# 808_Kick.net
KiCad netlist of a schematic drawn in EAGLE
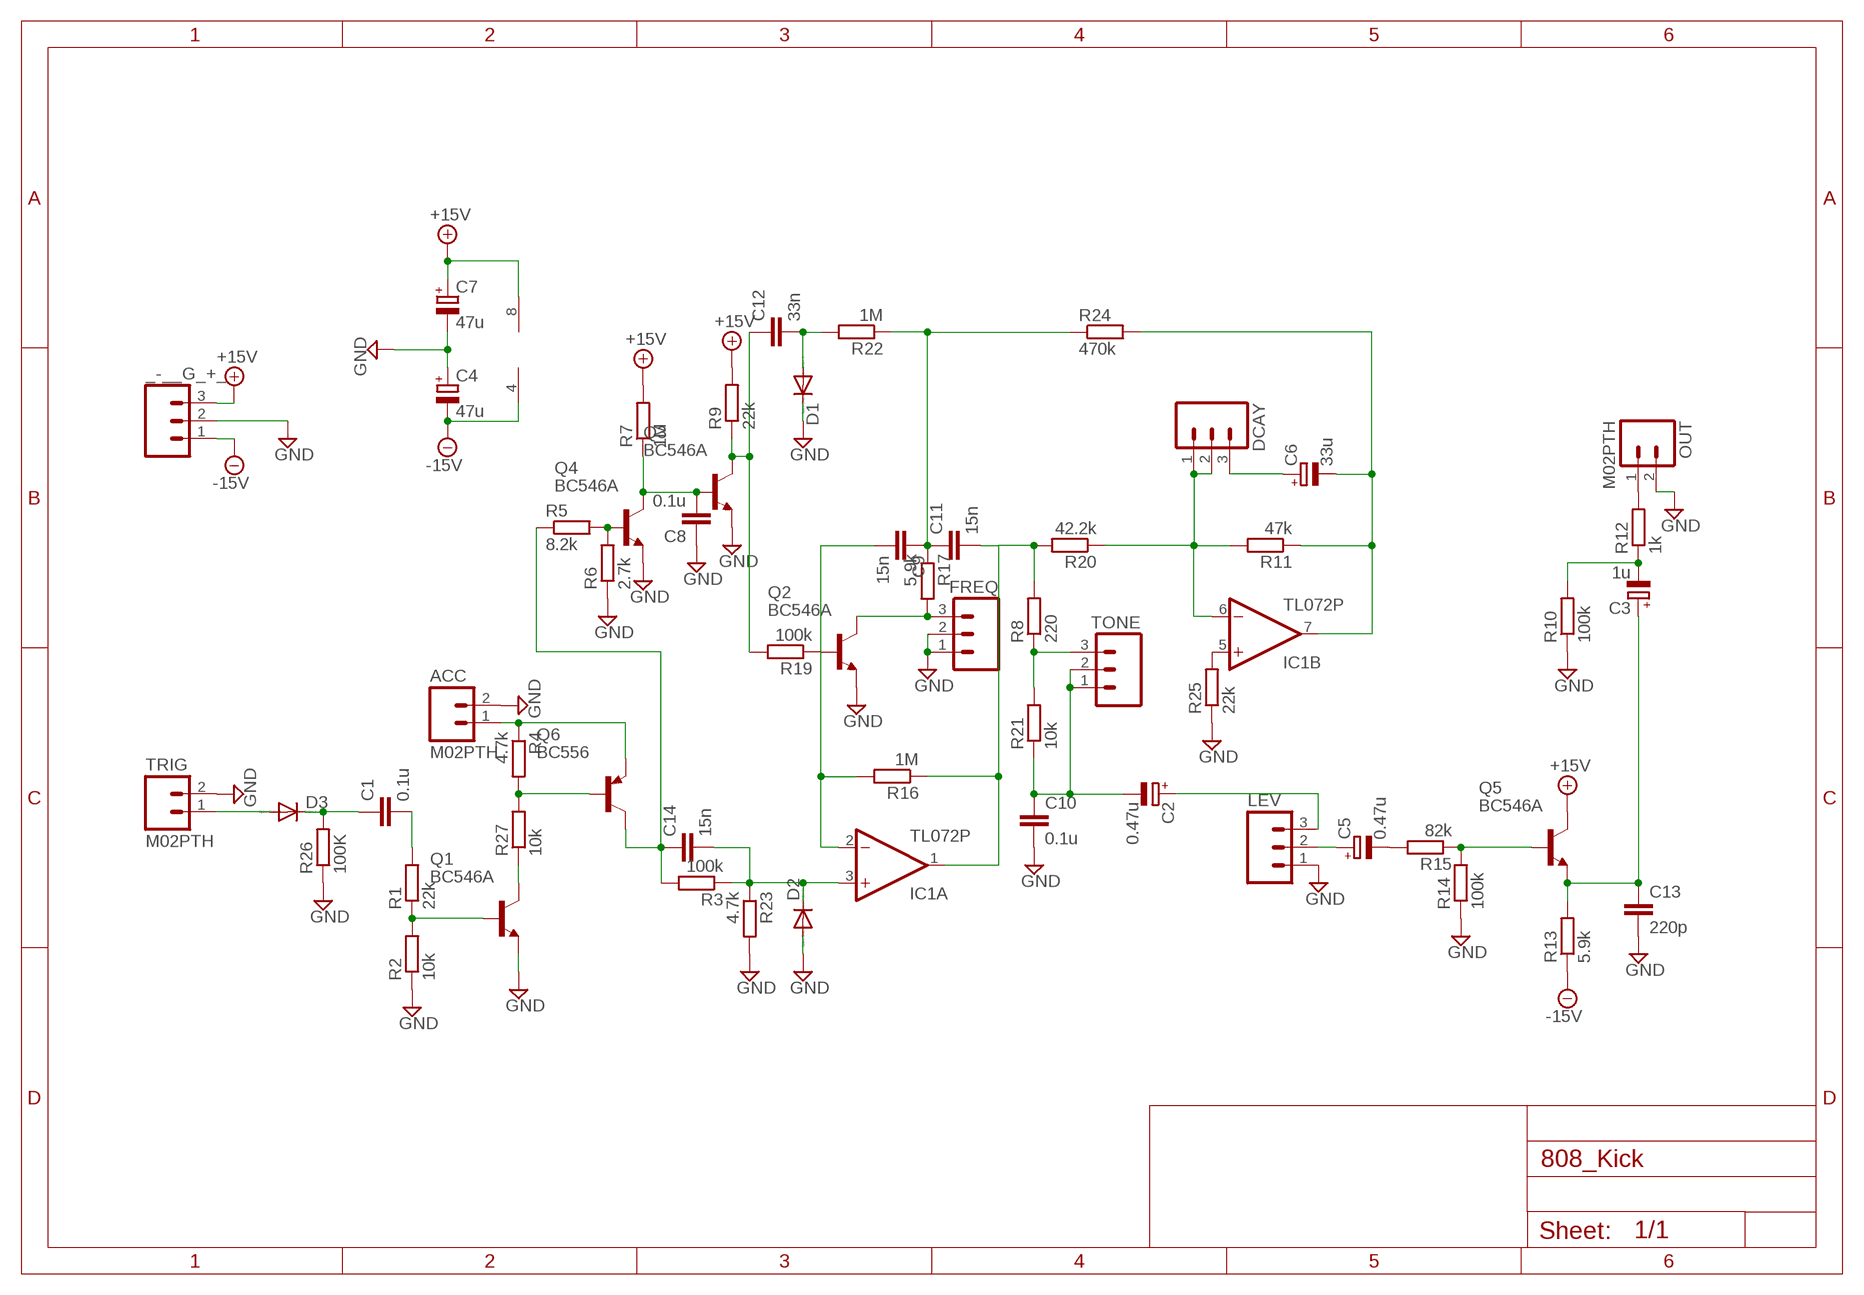
[diagram p0: schematic, sheet 1]

(export (version "E")
  (design (tool "Eeschema 10.0.6"))
  (components
    (comp (ref "ACC")
      (value "M02PTH")
      (footprint "eagle-import:1X02")
      (libsource (lib "eagle-import") (part "M02PTH"))
    )
    (comp (ref "C1")
      (value "0.1u")
      (footprint "eagle-import:C025-024X044")
      (libsource (lib "eagle-import") (part "C-EU025-024X044"))
    )
    (comp (ref "C2")
      (value "0.47u")
      (footprint "eagle-import:E2,5-6E")
      (libsource (lib "eagle-import") (part "CPOL-EUE2,5-6E"))
    )
    (comp (ref "C3")
      (value "1u")
      (footprint "eagle-import:E2,5-6E")
      (libsource (lib "eagle-import") (part "CPOL-EUE2,5-6E"))
    )
    (comp (ref "C4")
      (value "47u")
      (footprint "eagle-import:E2,5-6E")
      (libsource (lib "eagle-import") (part "CPOL-EUE2,5-6E"))
    )
    (comp (ref "C5")
      (value "0.47u")
      (footprint "eagle-import:E2,5-6E")
      (libsource (lib "eagle-import") (part "CPOL-EUE2,5-6E"))
    )
    (comp (ref "C6")
      (value "33u")
      (footprint "eagle-import:E2,5-6E")
      (libsource (lib "eagle-import") (part "CPOL-EUE2,5-6E"))
    )
    (comp (ref "C7")
      (value "47u")
      (footprint "eagle-import:E2,5-6E")
      (libsource (lib "eagle-import") (part "CPOL-EUE2,5-6E"))
    )
    (comp (ref "C8")
      (value "0.1u")
      (footprint "eagle-import:C025-024X044")
      (libsource (lib "eagle-import") (part "C-EU025-024X044"))
    )
    (comp (ref "C9")
      (value "15n")
      (footprint "eagle-import:C025-024X044")
      (libsource (lib "eagle-import") (part "C-EU025-024X044"))
    )
    (comp (ref "C10")
      (value "0.1u")
      (footprint "eagle-import:C025-024X044")
      (libsource (lib "eagle-import") (part "C-EU025-024X044"))
    )
    (comp (ref "C11")
      (value "15n")
      (footprint "eagle-import:C025-024X044")
      (libsource (lib "eagle-import") (part "C-EU025-024X044"))
    )
    (comp (ref "C12")
      (value "33n")
      (footprint "eagle-import:C025-024X044")
      (libsource (lib "eagle-import") (part "C-EU025-024X044"))
    )
    (comp (ref "C13")
      (value "220p")
      (footprint "eagle-import:C025-024X044")
      (libsource (lib "eagle-import") (part "C-EU025-024X044"))
    )
    (comp (ref "C14")
      (value "15n")
      (footprint "eagle-import:C025-024X044")
      (libsource (lib "eagle-import") (part "C-EU025-024X044"))
    )
    (comp (ref "D1")
      (value "DIODE-D-2.5")
      (footprint "eagle-import:D-2.5")
      (libsource (lib "eagle-import") (part "DIODE-D-2.5"))
    )
    (comp (ref "D2")
      (value "DIODE-D-2.5")
      (footprint "eagle-import:D-2.5")
      (libsource (lib "eagle-import") (part "DIODE-D-2.5"))
    )
    (comp (ref "D3")
      (value "DIODE-D-2.5")
      (footprint "eagle-import:D-2.5")
      (libsource (lib "eagle-import") (part "DIODE-D-2.5"))
    )
    (comp (ref "DCAY")
      (value "M03PTH")
      (footprint "eagle-import:1X03")
      (libsource (lib "eagle-import") (part "M03PTH"))
    )
    (comp (ref "FREQ")
      (value "M03PTH")
      (footprint "eagle-import:1X03")
      (libsource (lib "eagle-import") (part "M03PTH"))
    )
    (comp (ref "IC1")
      (value "TL072P")
      (footprint "eagle-import:DIL08")
      (libsource (lib "eagle-import") (part "TL072P"))
    )
    (comp (ref "LEV")
      (value "M03PTH")
      (footprint "eagle-import:1X03")
      (libsource (lib "eagle-import") (part "M03PTH"))
    )
    (comp (ref "OUT")
      (value "M02PTH")
      (footprint "eagle-import:1X02")
      (libsource (lib "eagle-import") (part "M02PTH"))
    )
    (comp (ref "Q1")
      (value "BC546A")
      (footprint "eagle-import:TO92-EBC")
      (libsource (lib "eagle-import") (part "BC546A"))
    )
    (comp (ref "Q2")
      (value "BC546A")
      (footprint "eagle-import:TO92-EBC")
      (libsource (lib "eagle-import") (part "BC546A"))
    )
    (comp (ref "Q3")
      (value "BC546A")
      (footprint "eagle-import:TO92-EBC")
      (libsource (lib "eagle-import") (part "BC546A"))
    )
    (comp (ref "Q4")
      (value "BC546A")
      (footprint "eagle-import:TO92-EBC")
      (libsource (lib "eagle-import") (part "BC546A"))
    )
    (comp (ref "Q5")
      (value "BC546A")
      (footprint "eagle-import:TO92-EBC")
      (libsource (lib "eagle-import") (part "BC546A"))
    )
    (comp (ref "Q6")
      (value "BC556")
      (footprint "eagle-import:TO92-EBC")
      (libsource (lib "eagle-import") (part "BC556"))
    )
    (comp (ref "R1")
      (value "22k")
      (footprint "eagle-import:0207_2V")
      (libsource (lib "eagle-import") (part "R-EU_0207/2V"))
    )
    (comp (ref "R2")
      (value "10k")
      (footprint "eagle-import:0207_2V")
      (libsource (lib "eagle-import") (part "R-EU_0207/2V"))
    )
    (comp (ref "R3")
      (value "100k")
      (footprint "eagle-import:0207_2V")
      (libsource (lib "eagle-import") (part "R-EU_0207/2V"))
    )
    (comp (ref "R4")
      (value "4.7k")
      (footprint "eagle-import:0207_2V")
      (libsource (lib "eagle-import") (part "R-EU_0207/2V"))
    )
    (comp (ref "R5")
      (value "8.2k")
      (footprint "eagle-import:0207_2V")
      (libsource (lib "eagle-import") (part "R-EU_0207/2V"))
    )
    (comp (ref "R6")
      (value "2.7k")
      (footprint "eagle-import:0207_2V")
      (libsource (lib "eagle-import") (part "R-EU_0207/2V"))
    )
    (comp (ref "R7")
      (value "1M")
      (footprint "eagle-import:0207_2V")
      (libsource (lib "eagle-import") (part "R-EU_0207/2V"))
    )
    (comp (ref "R8")
      (value "220")
      (footprint "eagle-import:0207_2V")
      (libsource (lib "eagle-import") (part "R-EU_0207/2V"))
    )
    (comp (ref "R9")
      (value "22k")
      (footprint "eagle-import:0207_2V")
      (libsource (lib "eagle-import") (part "R-EU_0207/2V"))
    )
    (comp (ref "R10")
      (value "100k")
      (footprint "eagle-import:0207_2V")
      (libsource (lib "eagle-import") (part "R-EU_0207/2V"))
    )
    (comp (ref "R11")
      (value "47k")
      (footprint "eagle-import:0207_2V")
      (libsource (lib "eagle-import") (part "R-EU_0207/2V"))
    )
    (comp (ref "R12")
      (value "1k")
      (footprint "eagle-import:0207_2V")
      (libsource (lib "eagle-import") (part "R-EU_0207/2V"))
    )
    (comp (ref "R13")
      (value "5.9k")
      (footprint "eagle-import:0207_2V")
      (libsource (lib "eagle-import") (part "R-EU_0207/2V"))
    )
    (comp (ref "R14")
      (value "100k")
      (footprint "eagle-import:0207_2V")
      (libsource (lib "eagle-import") (part "R-EU_0207/2V"))
    )
    (comp (ref "R15")
      (value "82k")
      (footprint "eagle-import:0207_2V")
      (libsource (lib "eagle-import") (part "R-EU_0207/2V"))
    )
    (comp (ref "R16")
      (value "1M")
      (footprint "eagle-import:0207_2V")
      (libsource (lib "eagle-import") (part "R-EU_0207/2V"))
    )
    (comp (ref "R17")
      (value "5.9k")
      (footprint "eagle-import:0207_2V")
      (libsource (lib "eagle-import") (part "R-EU_0207/2V"))
    )
    (comp (ref "R19")
      (value "100k")
      (footprint "eagle-import:0207_2V")
      (libsource (lib "eagle-import") (part "R-EU_0207/2V"))
    )
    (comp (ref "R20")
      (value "42.2k")
      (footprint "eagle-import:0207_2V")
      (libsource (lib "eagle-import") (part "R-EU_0207/2V"))
    )
    (comp (ref "R21")
      (value "10k")
      (footprint "eagle-import:0207_2V")
      (libsource (lib "eagle-import") (part "R-EU_0207/2V"))
    )
    (comp (ref "R22")
      (value "1M")
      (footprint "eagle-import:0207_2V")
      (libsource (lib "eagle-import") (part "R-EU_0207/2V"))
    )
    (comp (ref "R23")
      (value "4.7k")
      (footprint "eagle-import:0207_2V")
      (libsource (lib "eagle-import") (part "R-EU_0207/2V"))
    )
    (comp (ref "R24")
      (value "470k")
      (footprint "eagle-import:0207_2V")
      (libsource (lib "eagle-import") (part "R-EU_0207/2V"))
    )
    (comp (ref "R25")
      (value "22k")
      (footprint "eagle-import:0207_2V")
      (libsource (lib "eagle-import") (part "R-EU_0207/2V"))
    )
    (comp (ref "R26")
      (value "100K")
      (footprint "eagle-import:0207_2V")
      (libsource (lib "eagle-import") (part "R-EU_0207/2V"))
    )
    (comp (ref "R27")
      (value "10k")
      (footprint "eagle-import:0207_2V")
      (libsource (lib "eagle-import") (part "R-EU_0207/2V"))
    )
    (comp (ref "TONE")
      (value "M03PTH")
      (footprint "eagle-import:1X03")
      (libsource (lib "eagle-import") (part "M03PTH"))
    )
    (comp (ref "TRIG")
      (value "M02PTH")
      (footprint "eagle-import:1X02")
      (libsource (lib "eagle-import") (part "M02PTH"))
    )
    (comp (ref "_-__G_+_")
      (value "M03PTH")
      (footprint "eagle-import:1X03")
      (libsource (lib "eagle-import") (part "M03PTH"))
    )
  )
  (nets
    (net (code "1") (name "+15V") (class "Default")
      (node (ref "C7") (pin "+") (pinfunction "+_+") (pintype "passive"))
      (node (ref "IC1") (pin "8") (pinfunction "V+_8") (pintype "power_in"))
      (node (ref "Q5") (pin "C") (pinfunction "C_C") (pintype "passive"))
      (node (ref "R7") (pin "2") (pinfunction "2_2") (pintype "passive"))
      (node (ref "R9") (pin "2") (pinfunction "2_2") (pintype "passive"))
      (node (ref "_-__G_+_") (pin "3") (pinfunction "3_3") (pintype "passive"))
    )
    (net (code "2") (name "-15V") (class "Default")
      (node (ref "C4") (pin "-") (pinfunction "-_-") (pintype "passive"))
      (node (ref "IC1") (pin "4") (pinfunction "V-_4") (pintype "power_in"))
      (node (ref "R13") (pin "1") (pinfunction "1_1") (pintype "passive"))
      (node (ref "_-__G_+_") (pin "1") (pinfunction "1_1") (pintype "passive"))
    )
    (net (code "3") (name "GND") (class "Default")
      (node (ref "ACC") (pin "2") (pinfunction "2_2") (pintype "passive"))
      (node (ref "C10") (pin "2") (pinfunction "2_2") (pintype "passive"))
      (node (ref "C13") (pin "2") (pinfunction "2_2") (pintype "passive"))
      (node (ref "C4") (pin "+") (pinfunction "+_+") (pintype "passive"))
      (node (ref "C7") (pin "-") (pinfunction "-_-") (pintype "passive"))
      (node (ref "C8") (pin "1") (pinfunction "1_1") (pintype "passive"))
      (node (ref "D1") (pin "C") (pinfunction "C_C") (pintype "passive"))
      (node (ref "D2") (pin "A") (pinfunction "A_A") (pintype "passive"))
      (node (ref "FREQ") (pin "1") (pinfunction "1_1") (pintype "passive"))
      (node (ref "FREQ") (pin "2") (pinfunction "2_2") (pintype "passive"))
      (node (ref "LEV") (pin "1") (pinfunction "1_1") (pintype "passive"))
      (node (ref "OUT") (pin "2") (pinfunction "2_2") (pintype "passive"))
      (node (ref "Q1") (pin "E") (pinfunction "E_E") (pintype "passive"))
      (node (ref "Q2") (pin "E") (pinfunction "E_E") (pintype "passive"))
      (node (ref "Q3") (pin "E") (pinfunction "E_E") (pintype "passive"))
      (node (ref "Q4") (pin "E") (pinfunction "E_E") (pintype "passive"))
      (node (ref "R10") (pin "1") (pinfunction "1_1") (pintype "passive"))
      (node (ref "R14") (pin "1") (pinfunction "1_1") (pintype "passive"))
      (node (ref "R2") (pin "1") (pinfunction "1_1") (pintype "passive"))
      (node (ref "R23") (pin "2") (pinfunction "2_2") (pintype "passive"))
      (node (ref "R25") (pin "1") (pinfunction "1_1") (pintype "passive"))
      (node (ref "R26") (pin "1") (pinfunction "1_1") (pintype "passive"))
      (node (ref "R6") (pin "1") (pinfunction "1_1") (pintype "passive"))
      (node (ref "TRIG") (pin "2") (pinfunction "2_2") (pintype "passive"))
      (node (ref "_-__G_+_") (pin "2") (pinfunction "2_2") (pintype "passive"))
    )
    (net (code "4") (name "Net-(ACC-Pad1)") (class "Default")
      (node (ref "ACC") (pin "1") (pinfunction "1_1") (pintype "passive"))
      (node (ref "Q6") (pin "E") (pinfunction "E_E") (pintype "passive"))
      (node (ref "R4") (pin "1") (pinfunction "1_1") (pintype "passive"))
    )
    (net (code "5") (name "Net-(C1-Pad1)") (class "Default")
      (node (ref "C1") (pin "1") (pinfunction "1_1") (pintype "passive"))
      (node (ref "D3") (pin "C") (pinfunction "C_C") (pintype "passive"))
      (node (ref "R26") (pin "2") (pinfunction "2_2") (pintype "passive"))
    )
    (net (code "6") (name "Net-(C1-Pad2)") (class "Default")
      (node (ref "C1") (pin "2") (pinfunction "2_2") (pintype "passive"))
      (node (ref "R1") (pin "2") (pinfunction "2_2") (pintype "passive"))
    )
    (net (code "7") (name "Net-(C2-Pad+)") (class "Default")
      (node (ref "C2") (pin "+") (pinfunction "+_+") (pintype "passive"))
      (node (ref "LEV") (pin "3") (pinfunction "3_3") (pintype "passive"))
    )
    (net (code "8") (name "Net-(C3-Pad-)") (class "Default")
      (node (ref "C3") (pin "-") (pinfunction "-_-") (pintype "passive"))
      (node (ref "R10") (pin "2") (pinfunction "2_2") (pintype "passive"))
      (node (ref "R12") (pin "1") (pinfunction "1_1") (pintype "passive"))
    )
    (net (code "9") (name "Net-(C5-Pad+)") (class "Default")
      (node (ref "C5") (pin "+") (pinfunction "+_+") (pintype "passive"))
      (node (ref "LEV") (pin "2") (pinfunction "2_2") (pintype "passive"))
    )
    (net (code "10") (name "Net-(C5-Pad-)") (class "Default")
      (node (ref "C5") (pin "-") (pinfunction "-_-") (pintype "passive"))
      (node (ref "R15") (pin "2") (pinfunction "2_2") (pintype "passive"))
    )
    (net (code "11") (name "Net-(C6-Pad+)") (class "Default")
      (node (ref "C6") (pin "+") (pinfunction "+_+") (pintype "passive"))
      (node (ref "DCAY") (pin "3") (pinfunction "3_3") (pintype "passive"))
    )
    (net (code "12") (name "Net-(C8-Pad2)") (class "Default")
      (node (ref "C8") (pin "2") (pinfunction "2_2") (pintype "passive"))
      (node (ref "Q3") (pin "B") (pinfunction "B_B") (pintype "passive"))
      (node (ref "Q4") (pin "C") (pinfunction "C_C") (pintype "passive"))
      (node (ref "R7") (pin "1") (pinfunction "1_1") (pintype "passive"))
    )
    (net (code "13") (name "Net-(C10-Pad1)") (class "Default")
      (node (ref "C10") (pin "1") (pinfunction "1_1") (pintype "passive"))
      (node (ref "C2") (pin "-") (pinfunction "-_-") (pintype "passive"))
      (node (ref "R21") (pin "1") (pinfunction "1_1") (pintype "passive"))
      (node (ref "TONE") (pin "1") (pinfunction "1_1") (pintype "passive"))
      (node (ref "TONE") (pin "2") (pinfunction "2_2") (pintype "passive"))
    )
    (net (code "14") (name "Net-(C11-Pad1)") (class "Default")
      (node (ref "C11") (pin "1") (pinfunction "1_1") (pintype "passive"))
      (node (ref "C9") (pin "1") (pinfunction "1_1") (pintype "passive"))
      (node (ref "R17") (pin "1") (pinfunction "1_1") (pintype "passive"))
      (node (ref "R22") (pin "1") (pinfunction "1_1") (pintype "passive"))
      (node (ref "R24") (pin "1") (pinfunction "1_1") (pintype "passive"))
    )
    (net (code "15") (name "Net-(C12-Pad1)") (class "Default")
      (node (ref "C12") (pin "1") (pinfunction "1_1") (pintype "passive"))
      (node (ref "Q3") (pin "C") (pinfunction "C_C") (pintype "passive"))
      (node (ref "R19") (pin "2") (pinfunction "2_2") (pintype "passive"))
      (node (ref "R9") (pin "1") (pinfunction "1_1") (pintype "passive"))
    )
    (net (code "16") (name "Net-(C12-Pad2)") (class "Default")
      (node (ref "C12") (pin "2") (pinfunction "2_2") (pintype "passive"))
      (node (ref "D1") (pin "A") (pinfunction "A_A") (pintype "passive"))
      (node (ref "R22") (pin "2") (pinfunction "2_2") (pintype "passive"))
    )
    (net (code "17") (name "Net-(C13-Pad1)") (class "Default")
      (node (ref "C13") (pin "1") (pinfunction "1_1") (pintype "passive"))
      (node (ref "C3") (pin "+") (pinfunction "+_+") (pintype "passive"))
      (node (ref "Q5") (pin "E") (pinfunction "E_E") (pintype "passive"))
      (node (ref "R13") (pin "2") (pinfunction "2_2") (pintype "passive"))
    )
    (net (code "18") (name "Net-(C14-Pad1)") (class "Default")
      (node (ref "C14") (pin "1") (pinfunction "1_1") (pintype "passive"))
      (node (ref "Q6") (pin "C") (pinfunction "C_C") (pintype "passive"))
      (node (ref "R3") (pin "2") (pinfunction "2_2") (pintype "passive"))
      (node (ref "R5") (pin "1") (pinfunction "1_1") (pintype "passive"))
    )
    (net (code "19") (name "Net-(D3-PadA)") (class "Default")
      (node (ref "D3") (pin "A") (pinfunction "A_A") (pintype "passive"))
      (node (ref "TRIG") (pin "1") (pinfunction "1_1") (pintype "passive"))
    )
    (net (code "20") (name "Net-(FREQ-Pad3)") (class "Default")
      (node (ref "FREQ") (pin "3") (pinfunction "3_3") (pintype "passive"))
      (node (ref "Q2") (pin "C") (pinfunction "C_C") (pintype "passive"))
      (node (ref "R17") (pin "2") (pinfunction "2_2") (pintype "passive"))
    )
    (net (code "21") (name "Net-(IC1A-+IN)") (class "Default")
      (node (ref "C14") (pin "2") (pinfunction "2_2") (pintype "passive"))
      (node (ref "D2") (pin "C") (pinfunction "C_C") (pintype "passive"))
      (node (ref "IC1") (pin "3") (pinfunction "+IN_3") (pintype "input"))
      (node (ref "R23") (pin "1") (pinfunction "1_1") (pintype "passive"))
      (node (ref "R3") (pin "1") (pinfunction "1_1") (pintype "passive"))
    )
    (net (code "22") (name "Net-(IC1A--IN)") (class "Default")
      (node (ref "C9") (pin "2") (pinfunction "2_2") (pintype "passive"))
      (node (ref "IC1") (pin "2") (pinfunction "-IN_2") (pintype "input"))
      (node (ref "R16") (pin "2") (pinfunction "2_2") (pintype "passive"))
    )
    (net (code "23") (name "Net-(IC1A-OUT)") (class "Default")
      (node (ref "C11") (pin "2") (pinfunction "2_2") (pintype "passive"))
      (node (ref "IC1") (pin "1") (pinfunction "OUT_1") (pintype "output"))
      (node (ref "R16") (pin "1") (pinfunction "1_1") (pintype "passive"))
      (node (ref "R20") (pin "2") (pinfunction "2_2") (pintype "passive"))
      (node (ref "R8") (pin "2") (pinfunction "2_2") (pintype "passive"))
    )
    (net (code "24") (name "Net-(IC1B-+IN)") (class "Default")
      (node (ref "IC1") (pin "5") (pinfunction "+IN_5") (pintype "input"))
      (node (ref "R25") (pin "2") (pinfunction "2_2") (pintype "passive"))
    )
    (net (code "25") (name "Net-(IC1B--IN)") (class "Default")
      (node (ref "DCAY") (pin "1") (pinfunction "1_1") (pintype "passive"))
      (node (ref "DCAY") (pin "2") (pinfunction "2_2") (pintype "passive"))
      (node (ref "IC1") (pin "6") (pinfunction "-IN_6") (pintype "input"))
      (node (ref "R11") (pin "2") (pinfunction "2_2") (pintype "passive"))
      (node (ref "R20") (pin "1") (pinfunction "1_1") (pintype "passive"))
    )
    (net (code "26") (name "Net-(IC1B-OUT)") (class "Default")
      (node (ref "C6") (pin "-") (pinfunction "-_-") (pintype "passive"))
      (node (ref "IC1") (pin "7") (pinfunction "OUT_7") (pintype "output"))
      (node (ref "R11") (pin "1") (pinfunction "1_1") (pintype "passive"))
      (node (ref "R24") (pin "2") (pinfunction "2_2") (pintype "passive"))
    )
    (net (code "27") (name "Net-(OUT-Pad1)") (class "Default")
      (node (ref "OUT") (pin "1") (pinfunction "1_1") (pintype "passive"))
      (node (ref "R12") (pin "2") (pinfunction "2_2") (pintype "passive"))
    )
    (net (code "28") (name "Net-(Q1-PadB)") (class "Default")
      (node (ref "Q1") (pin "B") (pinfunction "B_B") (pintype "passive"))
      (node (ref "R1") (pin "1") (pinfunction "1_1") (pintype "passive"))
      (node (ref "R2") (pin "2") (pinfunction "2_2") (pintype "passive"))
    )
    (net (code "29") (name "Net-(Q1-PadC)") (class "Default")
      (node (ref "Q1") (pin "C") (pinfunction "C_C") (pintype "passive"))
      (node (ref "R27") (pin "1") (pinfunction "1_1") (pintype "passive"))
    )
    (net (code "30") (name "Net-(Q2-PadB)") (class "Default")
      (node (ref "Q2") (pin "B") (pinfunction "B_B") (pintype "passive"))
      (node (ref "R19") (pin "1") (pinfunction "1_1") (pintype "passive"))
    )
    (net (code "31") (name "Net-(Q4-PadB)") (class "Default")
      (node (ref "Q4") (pin "B") (pinfunction "B_B") (pintype "passive"))
      (node (ref "R5") (pin "2") (pinfunction "2_2") (pintype "passive"))
      (node (ref "R6") (pin "2") (pinfunction "2_2") (pintype "passive"))
    )
    (net (code "32") (name "Net-(Q5-PadB)") (class "Default")
      (node (ref "Q5") (pin "B") (pinfunction "B_B") (pintype "passive"))
      (node (ref "R14") (pin "2") (pinfunction "2_2") (pintype "passive"))
      (node (ref "R15") (pin "1") (pinfunction "1_1") (pintype "passive"))
    )
    (net (code "33") (name "Net-(Q6-PadB)") (class "Default")
      (node (ref "Q6") (pin "B") (pinfunction "B_B") (pintype "passive"))
      (node (ref "R27") (pin "2") (pinfunction "2_2") (pintype "passive"))
      (node (ref "R4") (pin "2") (pinfunction "2_2") (pintype "passive"))
    )
    (net (code "34") (name "Net-(R21-Pad2)") (class "Default")
      (node (ref "R21") (pin "2") (pinfunction "2_2") (pintype "passive"))
      (node (ref "R8") (pin "1") (pinfunction "1_1") (pintype "passive"))
      (node (ref "TONE") (pin "3") (pinfunction "3_3") (pintype "passive"))
    )
  )
)
